# Sheet1.net
KiCad netlist of a schematic drawn in Altium Designer
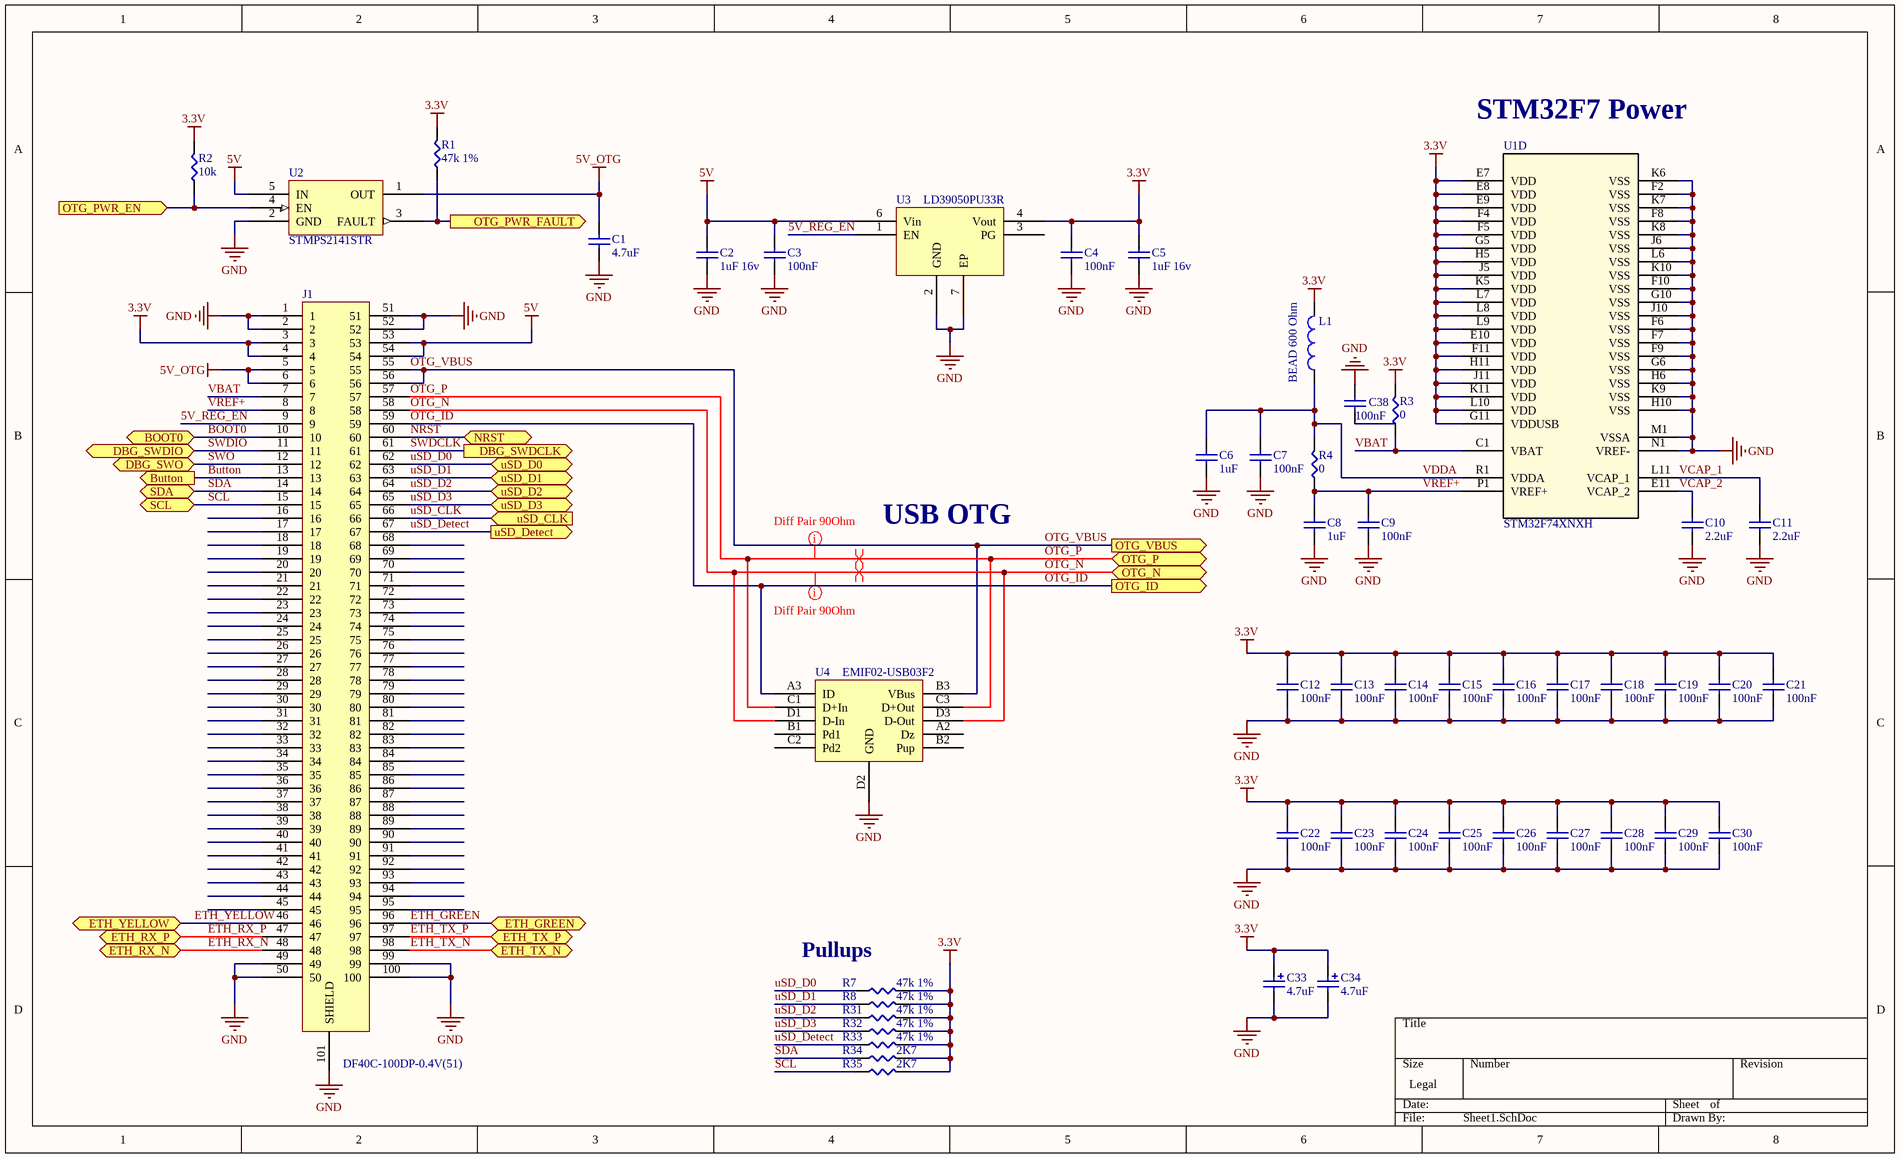
[diagram p0: Sheet1.SchDoc]

(export (version "E")
  (design (tool "Eeschema 10.0.6"))
  (components
    (comp (ref "C1")
      (value "4.7uF")
      (footprint "CAP0603X055M")
      (description "CAP CER 4.7UF 10V X5R 0603")
      (fields
        (field (name "MANUFACTURER") "Samsung Electro-Mechanics America, Inc.")
        (field (name "MANUFACTURER PART NUMBER") "CL10A475MP5LNNC")
      )
      (libsource (lib "Main") (part "CL10A475MP5LNNC"))
    )
    (comp (ref "C2")
      (value "1uF 16v")
      (footprint "CAP0603X055M")
      (description "CAP CER 1UF 16V Y5V 0603")
      (fields
        (field (name "MANUFACTURER") "Yageo")
        (field (name "MANUFACTURER PART NUMBER") "CC0603ZRY5V7BB105")
      )
      (libsource (lib "Main") (part "CC0603ZRY5V7BB105"))
    )
    (comp (ref "C3")
      (value "100nF")
      (footprint "CAP0402X04M")
      (description "CAP CER 0.1UF 16V X7R 0402")
      (fields
        (field (name "MANUFACTURER") "Murata Electronics North America")
        (field (name "MANUFACTURER PART NUMBER") "GRM155R71C104KA88J")
      )
      (libsource (lib "Main") (part "GRM155R71C104KA88J"))
    )
    (comp (ref "C4")
      (value "100nF")
      (footprint "CAP0402X04M")
      (description "CAP CER 0.1UF 16V X7R 0402")
      (fields
        (field (name "MANUFACTURER") "Murata Electronics North America")
        (field (name "MANUFACTURER PART NUMBER") "GRM155R71C104KA88J")
      )
      (libsource (lib "Main") (part "GRM155R71C104KA88J"))
    )
    (comp (ref "C5")
      (value "1uF 16v")
      (footprint "CAP0603X055M")
      (description "CAP CER 1UF 16V Y5V 0603")
      (fields
        (field (name "MANUFACTURER") "Yageo")
        (field (name "MANUFACTURER PART NUMBER") "CC0603ZRY5V7BB105")
      )
      (libsource (lib "Main") (part "CC0603ZRY5V7BB105"))
    )
    (comp (ref "C6")
      (value "1uF")
      (footprint "CAP0402X04M")
      (description "CAP CER 1UF 6.3V X5R 0402")
      (fields
        (field (name "MANUFACTURER") "Murata Electronics North America")
        (field (name "MANUFACTURER PART NUMBER") "GRM155R60J105KE19D")
      )
      (libsource (lib "Main") (part "GRM155R60J105KE19D"))
    )
    (comp (ref "C7")
      (value "100nF")
      (footprint "CAP0402X04M")
      (description "CAP CER 0.1UF 16V X7R 0402")
      (fields
        (field (name "MANUFACTURER") "Murata Electronics North America")
        (field (name "MANUFACTURER PART NUMBER") "GRM155R71C104KA88J")
      )
      (libsource (lib "Main") (part "GRM155R71C104KA88J"))
    )
    (comp (ref "C8")
      (value "1uF")
      (footprint "CAP0402X04M")
      (description "CAP CER 1UF 6.3V X5R 0402")
      (fields
        (field (name "MANUFACTURER") "Murata Electronics North America")
        (field (name "MANUFACTURER PART NUMBER") "GRM155R60J105KE19D")
      )
      (libsource (lib "Main") (part "GRM155R60J105KE19D"))
    )
    (comp (ref "C9")
      (value "100nF")
      (footprint "CAP0402X04M")
      (description "CAP CER 0.1UF 16V X7R 0402")
      (fields
        (field (name "MANUFACTURER") "Murata Electronics North America")
        (field (name "MANUFACTURER PART NUMBER") "GRM155R71C104KA88J")
      )
      (libsource (lib "Main") (part "GRM155R71C104KA88J"))
    )
    (comp (ref "C10")
      (value "2.2uF")
      (footprint "CAP0402X04ROUND")
      (description "CAP CER 2.2UF 6.3V X5R 0402")
      (fields
        (field (name "MANUFACTURER") "AVX Corporation")
        (field (name "MANUFACTURER PART NUMBER") "04026D225KAT2A")
      )
      (libsource (lib "Main") (part "04026D225KAT2A"))
    )
    (comp (ref "C11")
      (value "2.2uF")
      (footprint "CAP0402X04ROUND")
      (description "CAP CER 2.2UF 6.3V X5R 0402")
      (fields
        (field (name "MANUFACTURER") "AVX Corporation")
        (field (name "MANUFACTURER PART NUMBER") "04026D225KAT2A")
      )
      (libsource (lib "Main") (part "04026D225KAT2A"))
    )
    (comp (ref "C12")
      (value "100nF")
      (footprint "CAP0402X04ROUND")
      (description "CAP CER 0.1UF 16V X7R 0402")
      (fields
        (field (name "MANUFACTURER") "Murata Electronics North America")
        (field (name "MANUFACTURER PART NUMBER") "GRM155R71C104KA88J")
      )
      (libsource (lib "Main") (part "GRM155R71C104KA88J"))
    )
    (comp (ref "C13")
      (value "100nF")
      (footprint "CAP0402X04ROUND")
      (description "CAP CER 0.1UF 16V X7R 0402")
      (fields
        (field (name "MANUFACTURER") "Murata Electronics North America")
        (field (name "MANUFACTURER PART NUMBER") "GRM155R71C104KA88J")
      )
      (libsource (lib "Main") (part "GRM155R71C104KA88J"))
    )
    (comp (ref "C14")
      (value "100nF")
      (footprint "CAP0402X04ROUND")
      (description "CAP CER 0.1UF 16V X7R 0402")
      (fields
        (field (name "MANUFACTURER") "Murata Electronics North America")
        (field (name "MANUFACTURER PART NUMBER") "GRM155R71C104KA88J")
      )
      (libsource (lib "Main") (part "GRM155R71C104KA88J"))
    )
    (comp (ref "C15")
      (value "100nF")
      (footprint "CAP0402X04ROUND")
      (description "CAP CER 0.1UF 16V X7R 0402")
      (fields
        (field (name "MANUFACTURER") "Murata Electronics North America")
        (field (name "MANUFACTURER PART NUMBER") "GRM155R71C104KA88J")
      )
      (libsource (lib "Main") (part "GRM155R71C104KA88J"))
    )
    (comp (ref "C16")
      (value "100nF")
      (footprint "CAP0402X04ROUND")
      (description "CAP CER 0.1UF 16V X7R 0402")
      (fields
        (field (name "MANUFACTURER") "Murata Electronics North America")
        (field (name "MANUFACTURER PART NUMBER") "GRM155R71C104KA88J")
      )
      (libsource (lib "Main") (part "GRM155R71C104KA88J"))
    )
    (comp (ref "C17")
      (value "100nF")
      (footprint "CAP0402X04ROUND")
      (description "CAP CER 0.1UF 16V X7R 0402")
      (fields
        (field (name "MANUFACTURER") "Murata Electronics North America")
        (field (name "MANUFACTURER PART NUMBER") "GRM155R71C104KA88J")
      )
      (libsource (lib "Main") (part "GRM155R71C104KA88J"))
    )
    (comp (ref "C18")
      (value "100nF")
      (footprint "CAP0402X04ROUND")
      (description "CAP CER 0.1UF 16V X7R 0402")
      (fields
        (field (name "MANUFACTURER") "Murata Electronics North America")
        (field (name "MANUFACTURER PART NUMBER") "GRM155R71C104KA88J")
      )
      (libsource (lib "Main") (part "GRM155R71C104KA88J"))
    )
    (comp (ref "C19")
      (value "100nF")
      (footprint "CAP0402X04ROUND")
      (description "CAP CER 0.1UF 16V X7R 0402")
      (fields
        (field (name "MANUFACTURER") "Murata Electronics North America")
        (field (name "MANUFACTURER PART NUMBER") "GRM155R71C104KA88J")
      )
      (libsource (lib "Main") (part "GRM155R71C104KA88J"))
    )
    (comp (ref "C20")
      (value "100nF")
      (footprint "CAP0402X04ROUND")
      (description "CAP CER 0.1UF 16V X7R 0402")
      (fields
        (field (name "MANUFACTURER") "Murata Electronics North America")
        (field (name "MANUFACTURER PART NUMBER") "GRM155R71C104KA88J")
      )
      (libsource (lib "Main") (part "GRM155R71C104KA88J"))
    )
    (comp (ref "C21")
      (value "100nF")
      (footprint "CAP0402X04ROUND")
      (description "CAP CER 0.1UF 16V X7R 0402")
      (fields
        (field (name "MANUFACTURER") "Murata Electronics North America")
        (field (name "MANUFACTURER PART NUMBER") "GRM155R71C104KA88J")
      )
      (libsource (lib "Main") (part "GRM155R71C104KA88J"))
    )
    (comp (ref "C22")
      (value "100nF")
      (footprint "CAP0402X04ROUND")
      (description "CAP CER 0.1UF 16V X7R 0402")
      (fields
        (field (name "MANUFACTURER") "Murata Electronics North America")
        (field (name "MANUFACTURER PART NUMBER") "GRM155R71C104KA88J")
      )
      (libsource (lib "Main") (part "GRM155R71C104KA88J"))
    )
    (comp (ref "C23")
      (value "100nF")
      (footprint "CAP0402X04ROUND")
      (description "CAP CER 0.1UF 16V X7R 0402")
      (fields
        (field (name "MANUFACTURER") "Murata Electronics North America")
        (field (name "MANUFACTURER PART NUMBER") "GRM155R71C104KA88J")
      )
      (libsource (lib "Main") (part "GRM155R71C104KA88J"))
    )
    (comp (ref "C24")
      (value "100nF")
      (footprint "CAP0402X04ROUND")
      (description "CAP CER 0.1UF 16V X7R 0402")
      (fields
        (field (name "MANUFACTURER") "Murata Electronics North America")
        (field (name "MANUFACTURER PART NUMBER") "GRM155R71C104KA88J")
      )
      (libsource (lib "Main") (part "GRM155R71C104KA88J"))
    )
    (comp (ref "C25")
      (value "100nF")
      (footprint "CAP0402X04ROUND")
      (description "CAP CER 0.1UF 16V X7R 0402")
      (fields
        (field (name "MANUFACTURER") "Murata Electronics North America")
        (field (name "MANUFACTURER PART NUMBER") "GRM155R71C104KA88J")
      )
      (libsource (lib "Main") (part "GRM155R71C104KA88J"))
    )
    (comp (ref "C26")
      (value "100nF")
      (footprint "CAP0402X04ROUND")
      (description "CAP CER 0.1UF 16V X7R 0402")
      (fields
        (field (name "MANUFACTURER") "Murata Electronics North America")
        (field (name "MANUFACTURER PART NUMBER") "GRM155R71C104KA88J")
      )
      (libsource (lib "Main") (part "GRM155R71C104KA88J"))
    )
    (comp (ref "C27")
      (value "100nF")
      (footprint "CAP0402X04ROUND")
      (description "CAP CER 0.1UF 16V X7R 0402")
      (fields
        (field (name "MANUFACTURER") "Murata Electronics North America")
        (field (name "MANUFACTURER PART NUMBER") "GRM155R71C104KA88J")
      )
      (libsource (lib "Main") (part "GRM155R71C104KA88J"))
    )
    (comp (ref "C28")
      (value "100nF")
      (footprint "CAP0402X04ROUND")
      (description "CAP CER 0.1UF 16V X7R 0402")
      (fields
        (field (name "MANUFACTURER") "Murata Electronics North America")
        (field (name "MANUFACTURER PART NUMBER") "GRM155R71C104KA88J")
      )
      (libsource (lib "Main") (part "GRM155R71C104KA88J"))
    )
    (comp (ref "C29")
      (value "100nF")
      (footprint "CAP0402X04ROUND")
      (description "CAP CER 0.1UF 16V X7R 0402")
      (fields
        (field (name "MANUFACTURER") "Murata Electronics North America")
        (field (name "MANUFACTURER PART NUMBER") "GRM155R71C104KA88J")
      )
      (libsource (lib "Main") (part "GRM155R71C104KA88J"))
    )
    (comp (ref "C30")
      (value "100nF")
      (footprint "CAP0402X04ROUND")
      (description "CAP CER 0.1UF 16V X7R 0402")
      (fields
        (field (name "MANUFACTURER") "Murata Electronics North America")
        (field (name "MANUFACTURER PART NUMBER") "GRM155R71C104KA88J")
      )
      (libsource (lib "Main") (part "GRM155R71C104KA88J"))
    )
    (comp (ref "C33")
      (value "4.7uF")
      (footprint "CAPPOL0805X07N")
      (description "CAP TANT 4.7UF 10V 20% 0805")
      (fields
        (field (name "MANUFACTURER") "AVX Corporation")
        (field (name "MANUFACTURER PART NUMBER") "F921A475MPA")
      )
      (libsource (lib "Main") (part "F921A475MPA"))
    )
    (comp (ref "C34")
      (value "4.7uF")
      (footprint "CAPPOL0805X07N")
      (description "CAP TANT 4.7UF 10V 20% 0805")
      (fields
        (field (name "MANUFACTURER") "AVX Corporation")
        (field (name "MANUFACTURER PART NUMBER") "F921A475MPA")
      )
      (libsource (lib "Main") (part "F921A475MPA"))
    )
    (comp (ref "C38")
      (value "100nF")
      (footprint "CAP0402X04M")
      (description "CAP CER 0.1UF 16V X7R 0402")
      (fields
        (field (name "MANUFACTURER") "Murata Electronics North America")
        (field (name "MANUFACTURER PART NUMBER") "GRM155R71C104KA88J")
      )
      (libsource (lib "Main") (part "GRM155R71C104KA88J"))
    )
    (comp (ref "J1")
      (value "DF40C-100DP-0.4V(51)")
      (footprint "DF40C-100DP-0.4V(51)")
      (description "CONN HDR 100POS 0.4MM SMD GOLD")
      (fields (field (name "MANUFACTURER") "Hirose Electric Co Ltd"))
      (libsource (lib "Main") (part "DF40C-100DP-0.4V(51)"))
    )
    (comp (ref "L1")
      (value "BEAD 600 Ohm")
      (footprint "IND0603X055M")
      (description "FERRITE BEAD 600 OHM 0603 1LN")
      (fields
        (field (name "MANUFACTURER") "Taiyo Yuden")
        (field (name "MANUFACTURER PART NUMBER") "BK1608HW601-T")
      )
      (libsource (lib "Main") (part "BK1608HW601-T"))
    )
    (comp (ref "R1")
      (value "47k 1%")
      (footprint "RES0402X04M")
      (description "RES SMD 47K OHM 1% 1/10W 0402")
      (fields
        (field (name "MANUFACTURER") "Panasonic Electronic Components")
        (field (name "MANUFACTURER PART NUMBER") "ERJ-2RKF4702X")
      )
      (libsource (lib "Main") (part "ERJ-2RKF4702X"))
    )
    (comp (ref "R2")
      (value "10k")
      (footprint "RES0402X04M")
      (description "RES SMD 10K OHM 1% 1/16W 0402")
      (fields
        (field (name "MANUFACTURER") "Yageo")
        (field (name "MANUFACTURER PART NUMBER") "RC0402FR-0710KL")
      )
      (libsource (lib "Main") (part "RC0402FR-0710KL"))
    )
    (comp (ref "R3")
      (value "0")
      (footprint "RES0805X07M")
      (description "RES SMD 0.0 OHM JUMPER 1/8W 0805")
      (fields
        (field (name "MANUFACTURER") "Yageo")
        (field (name "MANUFACTURER PART NUMBER") "RC0805JR-070RL")
      )
      (libsource (lib "Main") (part "RC0805JR-070RL"))
    )
    (comp (ref "R4")
      (value "0")
      (footprint "RES0805X07M")
      (description "RES SMD 0.0 OHM JUMPER 1/8W 0805")
      (fields
        (field (name "MANUFACTURER") "Yageo")
        (field (name "MANUFACTURER PART NUMBER") "RC0805JR-070RL")
      )
      (libsource (lib "Main") (part "RC0805JR-070RL"))
    )
    (comp (ref "R7")
      (value "47k 1%")
      (footprint "RES0402X04M")
      (description "RES SMD 47K OHM 1% 1/10W 0402")
      (fields
        (field (name "MANUFACTURER") "Panasonic Electronic Components")
        (field (name "MANUFACTURER PART NUMBER") "ERJ-2RKF4702X")
      )
      (libsource (lib "Main") (part "ERJ-2RKF4702X"))
    )
    (comp (ref "R8")
      (value "47k 1%")
      (footprint "RES0402X04M")
      (description "RES SMD 47K OHM 1% 1/10W 0402")
      (fields
        (field (name "MANUFACTURER") "Panasonic Electronic Components")
        (field (name "MANUFACTURER PART NUMBER") "ERJ-2RKF4702X")
      )
      (libsource (lib "Main") (part "ERJ-2RKF4702X"))
    )
    (comp (ref "R31")
      (value "47k 1%")
      (footprint "RES0402X04M")
      (description "RES SMD 47K OHM 1% 1/10W 0402")
      (fields
        (field (name "MANUFACTURER") "Panasonic Electronic Components")
        (field (name "MANUFACTURER PART NUMBER") "ERJ-2RKF4702X")
      )
      (libsource (lib "Main") (part "ERJ-2RKF4702X"))
    )
    (comp (ref "R32")
      (value "47k 1%")
      (footprint "RES0402X04M")
      (description "RES SMD 47K OHM 1% 1/10W 0402")
      (fields
        (field (name "MANUFACTURER") "Panasonic Electronic Components")
        (field (name "MANUFACTURER PART NUMBER") "ERJ-2RKF4702X")
      )
      (libsource (lib "Main") (part "ERJ-2RKF4702X"))
    )
    (comp (ref "R33")
      (value "47k 1%")
      (footprint "RES0402X04M")
      (description "RES SMD 47K OHM 1% 1/10W 0402")
      (fields
        (field (name "MANUFACTURER") "Panasonic Electronic Components")
        (field (name "MANUFACTURER PART NUMBER") "ERJ-2RKF4702X")
      )
      (libsource (lib "Main") (part "ERJ-2RKF4702X"))
    )
    (comp (ref "R34")
      (value "2K7")
      (footprint "RES0402X04M")
      (description "RES SMD 2.7K OHM 1% 1/10W 0402")
      (fields
        (field (name "MANUFACTURER") "Panasonic Electronic Components")
        (field (name "MANUFACTURER PART NUMBER") "ERJ-2RKF2701X")
      )
      (libsource (lib "Main") (part "ERJ-2RKF2701X"))
    )
    (comp (ref "R35")
      (value "2K7")
      (footprint "RES0402X04M")
      (description "RES SMD 2.7K OHM 1% 1/10W 0402")
      (fields
        (field (name "MANUFACTURER") "Panasonic Electronic Components")
        (field (name "MANUFACTURER PART NUMBER") "ERJ-2RKF2701X")
      )
      (libsource (lib "Main") (part "ERJ-2RKF2701X"))
    )
    (comp (ref "U1")
      (value "STM32F74XNXH")
      (footprint "TFBGA-216_13X13")
      (description "Imported")
      (fields
        (field (name "MANUFACTURER") "STMicroelectronics")
        (field (name "MANUFACTURER PART NUMBER") "STM32F746NGH6")
        (field (name "COPYRIGHT") "Copyright (C) 2016 Accelerated Designs. All rights reserved")
      )
      (libsource (lib "Main") (part "STM32F74XNXH"))
    )
    (comp (ref "U2")
      (value "STMPS2141STR")
      (footprint "SOT95P280X145-5N")
      (description "IC PWR SWITCH 1CH 500MA SOT23-5")
      (fields (field (name "MANUFACTURER") "STMicroelectronics"))
      (libsource (lib "Main") (part "STMPS2141STR"))
    )
    (comp (ref "U3")
      (value "LD39050PU33R")
      (footprint "LD39050")
      (description "IC REG LDO 3.3V 0.5A 6DFN")
      (fields (field (name "MANUFACTURER") "STMicroelectronics"))
      (libsource (lib "Main") (part "LD39050PU33R"))
    )
    (comp (ref "U4")
      (value "EMIF02-USB03F2")
      (footprint "EMIF02-USB03F2")
      (description "FILTER RC(PI) 33 OHM/20PF SMD")
      (fields (field (name "MANUFACTURER") "STMicroelectronics"))
      (libsource (lib "Main") (part "EMIF02-USB03F2"))
    )
  )
  (nets
    (net (code "1") (name "/5V_REG_EN") (class "Default")
      (node (ref "J1") (pin "9") (pinfunction "9_9") (pintype "passive"))
      (node (ref "U3") (pin "1") (pinfunction "EN_1") (pintype "passive"))
    )
    (net (code "2") (name "/BOOT0") (class "Default")
      (node (ref "J1") (pin "10") (pinfunction "10_10") (pintype "passive"))
    )
    (net (code "3") (name "/Button") (class "Default")
      (node (ref "J1") (pin "13") (pinfunction "13_13") (pintype "passive"))
    )
    (net (code "4") (name "/ETH_GREEN") (class "Default")
      (node (ref "J1") (pin "96") (pinfunction "96_96") (pintype "passive"))
    )
    (net (code "5") (name "/ETH_RX_N") (class "Default")
      (node (ref "J1") (pin "48") (pinfunction "48_48") (pintype "passive"))
    )
    (net (code "6") (name "/ETH_RX_P") (class "Default")
      (node (ref "J1") (pin "47") (pinfunction "47_47") (pintype "passive"))
    )
    (net (code "7") (name "/ETH_TX_N") (class "Default")
      (node (ref "J1") (pin "98") (pinfunction "98_98") (pintype "passive"))
    )
    (net (code "8") (name "/ETH_TX_P") (class "Default")
      (node (ref "J1") (pin "97") (pinfunction "97_97") (pintype "passive"))
    )
    (net (code "9") (name "/ETH_YELLOW") (class "Default")
      (node (ref "J1") (pin "46") (pinfunction "46_46") (pintype "passive"))
    )
    (net (code "10") (name "/NRST") (class "Default")
      (node (ref "J1") (pin "60") (pinfunction "60_60") (pintype "passive"))
    )
    (net (code "11") (name "/OTG_ID") (class "Default")
      (node (ref "J1") (pin "59") (pinfunction "59_59") (pintype "passive"))
      (node (ref "U4") (pin "A3") (pinfunction "ID_A3") (pintype "passive"))
    )
    (net (code "12") (name "/OTG_N") (class "Default")
      (node (ref "J1") (pin "58") (pinfunction "58_58") (pintype "passive"))
      (node (ref "U4") (pin "D1") (pinfunction "D-In_D1") (pintype "passive"))
      (node (ref "U4") (pin "D3") (pinfunction "D-Out_D3") (pintype "passive"))
    )
    (net (code "13") (name "/OTG_P") (class "Default")
      (node (ref "J1") (pin "57") (pinfunction "57_57") (pintype "passive"))
      (node (ref "U4") (pin "C1") (pinfunction "D+In_C1") (pintype "passive"))
      (node (ref "U4") (pin "C3") (pinfunction "D+Out_C3") (pintype "passive"))
    )
    (net (code "14") (name "/OTG_PWR_EN") (class "Default")
      (node (ref "R2") (pin "1") (pinfunction "1_1") (pintype "passive"))
      (node (ref "U2") (pin "4") (pinfunction "EN_4") (pintype "input"))
    )
    (net (code "15") (name "/OTG_PWR_FAULT") (class "Default")
      (node (ref "R1") (pin "1") (pinfunction "1_1") (pintype "passive"))
      (node (ref "U2") (pin "3") (pinfunction "FAULT_3") (pintype "output"))
    )
    (net (code "16") (name "/OTG_VBUS") (class "Default")
      (node (ref "J1") (pin "55") (pinfunction "55_55") (pintype "passive"))
      (node (ref "J1") (pin "56") (pinfunction "56_56") (pintype "passive"))
      (node (ref "U4") (pin "B3") (pinfunction "VBus_B3") (pintype "passive"))
    )
    (net (code "17") (name "/SCL") (class "Default")
      (node (ref "J1") (pin "15") (pinfunction "15_15") (pintype "passive"))
      (node (ref "R35") (pin "1") (pinfunction "1_1") (pintype "passive"))
    )
    (net (code "18") (name "/SDA") (class "Default")
      (node (ref "J1") (pin "14") (pinfunction "14_14") (pintype "passive"))
      (node (ref "R34") (pin "1") (pinfunction "1_1") (pintype "passive"))
    )
    (net (code "19") (name "/SWDCLK") (class "Default")
      (node (ref "J1") (pin "61") (pinfunction "61_61") (pintype "passive"))
    )
    (net (code "20") (name "/SWDIO") (class "Default")
      (node (ref "J1") (pin "11") (pinfunction "11_11") (pintype "passive"))
    )
    (net (code "21") (name "/SWO") (class "Default")
      (node (ref "J1") (pin "12") (pinfunction "12_12") (pintype "passive"))
    )
    (net (code "22") (name "/VBAT") (class "Default")
      (node (ref "J1") (pin "7") (pinfunction "7_7") (pintype "passive"))
      (node (ref "R3") (pin "1") (pinfunction "1_1") (pintype "passive"))
      (node (ref "U1") (pin "C1") (pinfunction "VBAT_C1") (pintype "power_in"))
    )
    (net (code "23") (name "/VCAP_1") (class "Default")
      (node (ref "C11") (pin "2") (pinfunction "2_2") (pintype "passive"))
      (node (ref "U1") (pin "L11") (pinfunction "VCAP_1_L11") (pintype "power_in"))
    )
    (net (code "24") (name "/VCAP_2") (class "Default")
      (node (ref "C10") (pin "2") (pinfunction "2_2") (pintype "passive"))
      (node (ref "U1") (pin "E11") (pinfunction "VCAP_2_E11") (pintype "power_in"))
    )
    (net (code "25") (name "/VDDA") (class "Default")
      (node (ref "C6") (pin "2") (pinfunction "2_2") (pintype "passive"))
      (node (ref "C7") (pin "2") (pinfunction "2_2") (pintype "passive"))
      (node (ref "L1") (pin "1") (pinfunction "1_1") (pintype "passive"))
      (node (ref "R4") (pin "2") (pinfunction "2_2") (pintype "passive"))
      (node (ref "U1") (pin "R1") (pinfunction "VDDA_R1") (pintype "power_in"))
    )
    (net (code "26") (name "/VREF+") (class "Default")
      (node (ref "C8") (pin "2") (pinfunction "2_2") (pintype "passive"))
      (node (ref "C9") (pin "2") (pinfunction "2_2") (pintype "passive"))
      (node (ref "J1") (pin "8") (pinfunction "8_8") (pintype "passive"))
      (node (ref "R4") (pin "1") (pinfunction "1_1") (pintype "passive"))
      (node (ref "U1") (pin "P1") (pinfunction "VREF+_P1") (pintype "power_in"))
    )
    (net (code "27") (name "/uSD_CLK") (class "Default")
      (node (ref "J1") (pin "66") (pinfunction "66_66") (pintype "passive"))
    )
    (net (code "28") (name "/uSD_D0") (class "Default")
      (node (ref "J1") (pin "62") (pinfunction "62_62") (pintype "passive"))
      (node (ref "R7") (pin "1") (pinfunction "1_1") (pintype "passive"))
    )
    (net (code "29") (name "/uSD_D1") (class "Default")
      (node (ref "J1") (pin "63") (pinfunction "63_63") (pintype "passive"))
      (node (ref "R8") (pin "1") (pinfunction "1_1") (pintype "passive"))
    )
    (net (code "30") (name "/uSD_D2") (class "Default")
      (node (ref "J1") (pin "64") (pinfunction "64_64") (pintype "passive"))
      (node (ref "R31") (pin "1") (pinfunction "1_1") (pintype "passive"))
    )
    (net (code "31") (name "/uSD_D3") (class "Default")
      (node (ref "J1") (pin "65") (pinfunction "65_65") (pintype "passive"))
      (node (ref "R32") (pin "1") (pinfunction "1_1") (pintype "passive"))
    )
    (net (code "32") (name "/uSD_Detect") (class "Default")
      (node (ref "J1") (pin "67") (pinfunction "67_67") (pintype "passive"))
      (node (ref "R33") (pin "1") (pinfunction "1_1") (pintype "passive"))
    )
    (net (code "33") (name "3.3V") (class "Default")
      (node (ref "C12") (pin "2") (pinfunction "2_2") (pintype "passive"))
      (node (ref "C13") (pin "2") (pinfunction "2_2") (pintype "passive"))
      (node (ref "C14") (pin "2") (pinfunction "2_2") (pintype "passive"))
      (node (ref "C15") (pin "2") (pinfunction "2_2") (pintype "passive"))
      (node (ref "C16") (pin "2") (pinfunction "2_2") (pintype "passive"))
      (node (ref "C17") (pin "2") (pinfunction "2_2") (pintype "passive"))
      (node (ref "C18") (pin "2") (pinfunction "2_2") (pintype "passive"))
      (node (ref "C19") (pin "2") (pinfunction "2_2") (pintype "passive"))
      (node (ref "C20") (pin "2") (pinfunction "2_2") (pintype "passive"))
      (node (ref "C21") (pin "2") (pinfunction "2_2") (pintype "passive"))
      (node (ref "C22") (pin "2") (pinfunction "2_2") (pintype "passive"))
      (node (ref "C23") (pin "2") (pinfunction "2_2") (pintype "passive"))
      (node (ref "C24") (pin "2") (pinfunction "2_2") (pintype "passive"))
      (node (ref "C25") (pin "2") (pinfunction "2_2") (pintype "passive"))
      (node (ref "C26") (pin "2") (pinfunction "2_2") (pintype "passive"))
      (node (ref "C27") (pin "2") (pinfunction "2_2") (pintype "passive"))
      (node (ref "C28") (pin "2") (pinfunction "2_2") (pintype "passive"))
      (node (ref "C29") (pin "2") (pinfunction "2_2") (pintype "passive"))
      (node (ref "C30") (pin "2") (pinfunction "2_2") (pintype "passive"))
      (node (ref "C33") (pin "1") (pinfunction "1_1") (pintype "passive"))
      (node (ref "C34") (pin "1") (pinfunction "1_1") (pintype "passive"))
      (node (ref "C4") (pin "2") (pinfunction "2_2") (pintype "passive"))
      (node (ref "C5") (pin "2") (pinfunction "2_2") (pintype "passive"))
      (node (ref "J1") (pin "3") (pinfunction "3_3") (pintype "passive"))
      (node (ref "J1") (pin "4") (pinfunction "4_4") (pintype "passive"))
      (node (ref "L1") (pin "2") (pinfunction "2_2") (pintype "passive"))
      (node (ref "R1") (pin "2") (pinfunction "2_2") (pintype "passive"))
      (node (ref "R2") (pin "2") (pinfunction "2_2") (pintype "passive"))
      (node (ref "R3") (pin "2") (pinfunction "2_2") (pintype "passive"))
      (node (ref "R31") (pin "2") (pinfunction "2_2") (pintype "passive"))
      (node (ref "R32") (pin "2") (pinfunction "2_2") (pintype "passive"))
      (node (ref "R33") (pin "2") (pinfunction "2_2") (pintype "passive"))
      (node (ref "R34") (pin "2") (pinfunction "2_2") (pintype "passive"))
      (node (ref "R35") (pin "2") (pinfunction "2_2") (pintype "passive"))
      (node (ref "R7") (pin "2") (pinfunction "2_2") (pintype "passive"))
      (node (ref "R8") (pin "2") (pinfunction "2_2") (pintype "passive"))
      (node (ref "U1") (pin "E10") (pinfunction "VDD_E10") (pintype "power_in"))
      (node (ref "U1") (pin "E7") (pinfunction "VDD_E7") (pintype "power_in"))
      (node (ref "U1") (pin "E8") (pinfunction "VDD_E8") (pintype "power_in"))
      (node (ref "U1") (pin "E9") (pinfunction "VDD_E9") (pintype "power_in"))
      (node (ref "U1") (pin "F11") (pinfunction "VDD_F11") (pintype "power_in"))
      (node (ref "U1") (pin "F4") (pinfunction "VDD_F4") (pintype "power_in"))
      (node (ref "U1") (pin "F5") (pinfunction "VDD_F5") (pintype "power_in"))
      (node (ref "U1") (pin "G11") (pinfunction "VDDUSB_G11") (pintype "power_in"))
      (node (ref "U1") (pin "G5") (pinfunction "VDD_G5") (pintype "power_in"))
      (node (ref "U1") (pin "H11") (pinfunction "VDD_H11") (pintype "power_in"))
      (node (ref "U1") (pin "H5") (pinfunction "VDD_H5") (pintype "power_in"))
      (node (ref "U1") (pin "J11") (pinfunction "VDD_J11") (pintype "power_in"))
      (node (ref "U1") (pin "J5") (pinfunction "VDD_J5") (pintype "power_in"))
      (node (ref "U1") (pin "K11") (pinfunction "VDD_K11") (pintype "power_in"))
      (node (ref "U1") (pin "K5") (pinfunction "VDD_K5") (pintype "power_in"))
      (node (ref "U1") (pin "L10") (pinfunction "VDD_L10") (pintype "power_in"))
      (node (ref "U1") (pin "L7") (pinfunction "VDD_L7") (pintype "power_in"))
      (node (ref "U1") (pin "L8") (pinfunction "VDD_L8") (pintype "power_in"))
      (node (ref "U1") (pin "L9") (pinfunction "VDD_L9") (pintype "power_in"))
      (node (ref "U3") (pin "4") (pinfunction "Vout_4") (pintype "passive"))
    )
    (net (code "34") (name "5V") (class "Default")
      (node (ref "C2") (pin "2") (pinfunction "2_2") (pintype "passive"))
      (node (ref "C3") (pin "2") (pinfunction "2_2") (pintype "passive"))
      (node (ref "J1") (pin "53") (pinfunction "53_53") (pintype "passive"))
      (node (ref "J1") (pin "54") (pinfunction "54_54") (pintype "passive"))
      (node (ref "U2") (pin "5") (pinfunction "IN_5") (pintype "power_in"))
      (node (ref "U3") (pin "6") (pinfunction "Vin_6") (pintype "passive"))
    )
    (net (code "35") (name "5V_OTG") (class "Default")
      (node (ref "C1") (pin "2") (pinfunction "2_2") (pintype "passive"))
      (node (ref "J1") (pin "5") (pinfunction "5_5") (pintype "passive"))
      (node (ref "J1") (pin "6") (pinfunction "6_6") (pintype "passive"))
      (node (ref "U2") (pin "1") (pinfunction "OUT_1") (pintype "power_in"))
    )
    (net (code "36") (name "GND") (class "Default")
      (node (ref "C1") (pin "1") (pinfunction "1_1") (pintype "passive"))
      (node (ref "C10") (pin "1") (pinfunction "1_1") (pintype "passive"))
      (node (ref "C11") (pin "1") (pinfunction "1_1") (pintype "passive"))
      (node (ref "C12") (pin "1") (pinfunction "1_1") (pintype "passive"))
      (node (ref "C13") (pin "1") (pinfunction "1_1") (pintype "passive"))
      (node (ref "C14") (pin "1") (pinfunction "1_1") (pintype "passive"))
      (node (ref "C15") (pin "1") (pinfunction "1_1") (pintype "passive"))
      (node (ref "C16") (pin "1") (pinfunction "1_1") (pintype "passive"))
      (node (ref "C17") (pin "1") (pinfunction "1_1") (pintype "passive"))
      (node (ref "C18") (pin "1") (pinfunction "1_1") (pintype "passive"))
      (node (ref "C19") (pin "1") (pinfunction "1_1") (pintype "passive"))
      (node (ref "C2") (pin "1") (pinfunction "1_1") (pintype "passive"))
      (node (ref "C20") (pin "1") (pinfunction "1_1") (pintype "passive"))
      (node (ref "C21") (pin "1") (pinfunction "1_1") (pintype "passive"))
      (node (ref "C22") (pin "1") (pinfunction "1_1") (pintype "passive"))
      (node (ref "C23") (pin "1") (pinfunction "1_1") (pintype "passive"))
      (node (ref "C24") (pin "1") (pinfunction "1_1") (pintype "passive"))
      (node (ref "C25") (pin "1") (pinfunction "1_1") (pintype "passive"))
      (node (ref "C26") (pin "1") (pinfunction "1_1") (pintype "passive"))
      (node (ref "C27") (pin "1") (pinfunction "1_1") (pintype "passive"))
      (node (ref "C28") (pin "1") (pinfunction "1_1") (pintype "passive"))
      (node (ref "C29") (pin "1") (pinfunction "1_1") (pintype "passive"))
      (node (ref "C3") (pin "1") (pinfunction "1_1") (pintype "passive"))
      (node (ref "C30") (pin "1") (pinfunction "1_1") (pintype "passive"))
      (node (ref "C33") (pin "2") (pinfunction "2_2") (pintype "passive"))
      (node (ref "C34") (pin "2") (pinfunction "2_2") (pintype "passive"))
      (node (ref "C38") (pin "2") (pinfunction "2_2") (pintype "passive"))
      (node (ref "C4") (pin "1") (pinfunction "1_1") (pintype "passive"))
      (node (ref "C5") (pin "1") (pinfunction "1_1") (pintype "passive"))
      (node (ref "C6") (pin "1") (pinfunction "1_1") (pintype "passive"))
      (node (ref "C7") (pin "1") (pinfunction "1_1") (pintype "passive"))
      (node (ref "C8") (pin "1") (pinfunction "1_1") (pintype "passive"))
      (node (ref "C9") (pin "1") (pinfunction "1_1") (pintype "passive"))
      (node (ref "J1") (pin "1") (pinfunction "1_1") (pintype "passive"))
      (node (ref "J1") (pin "100") (pinfunction "100_100") (pintype "passive"))
      (node (ref "J1") (pin "101") (pinfunction "SHIELD_101") (pintype "passive"))
      (node (ref "J1") (pin "2") (pinfunction "2_2") (pintype "passive"))
      (node (ref "J1") (pin "49") (pinfunction "49_49") (pintype "passive"))
      (node (ref "J1") (pin "50") (pinfunction "50_50") (pintype "passive"))
      (node (ref "J1") (pin "51") (pinfunction "51_51") (pintype "passive"))
      (node (ref "J1") (pin "52") (pinfunction "52_52") (pintype "passive"))
      (node (ref "J1") (pin "99") (pinfunction "99_99") (pintype "passive"))
      (node (ref "U1") (pin "F10") (pinfunction "VSS_F10") (pintype "power_in"))
      (node (ref "U1") (pin "F2") (pinfunction "VSS_F2") (pintype "power_in"))
      (node (ref "U1") (pin "F6") (pinfunction "VSS_F6") (pintype "power_in"))
      (node (ref "U1") (pin "F7") (pinfunction "VSS_F7") (pintype "power_in"))
      (node (ref "U1") (pin "F8") (pinfunction "VSS_F8") (pintype "power_in"))
      (node (ref "U1") (pin "F9") (pinfunction "VSS_F9") (pintype "power_in"))
      (node (ref "U1") (pin "G10") (pinfunction "VSS_G10") (pintype "power_in"))
      (node (ref "U1") (pin "G6") (pinfunction "VSS_G6") (pintype "power_in"))
      (node (ref "U1") (pin "H10") (pinfunction "VSS_H10") (pintype "power_in"))
      (node (ref "U1") (pin "H6") (pinfunction "VSS_H6") (pintype "power_in"))
      (node (ref "U1") (pin "J10") (pinfunction "VSS_J10") (pintype "power_in"))
      (node (ref "U1") (pin "J6") (pinfunction "VSS_J6") (pintype "power_in"))
      (node (ref "U1") (pin "K10") (pinfunction "VSS_K10") (pintype "power_in"))
      (node (ref "U1") (pin "K6") (pinfunction "VSS_K6") (pintype "power_in"))
      (node (ref "U1") (pin "K7") (pinfunction "VSS_K7") (pintype "power_in"))
      (node (ref "U1") (pin "K8") (pinfunction "VSS_K8") (pintype "power_in"))
      (node (ref "U1") (pin "K9") (pinfunction "VSS_K9") (pintype "power_in"))
      (node (ref "U1") (pin "L6") (pinfunction "VSS_L6") (pintype "power_in"))
      (node (ref "U1") (pin "M1") (pinfunction "VSSA_M1") (pintype "power_in"))
      (node (ref "U1") (pin "N1") (pinfunction "VREF-_N1") (pintype "power_in"))
      (node (ref "U2") (pin "2") (pinfunction "GND_2") (pintype "power_in"))
      (node (ref "U3") (pin "2") (pinfunction "GND_2") (pintype "passive"))
      (node (ref "U3") (pin "7") (pinfunction "EP_7") (pintype "passive"))
      (node (ref "U4") (pin "D2") (pinfunction "GND_D2") (pintype "power_in"))
    )
    (net (code "37") (name "unconnected-(C38-Pad1)") (class "Default")
      (node (ref "C38") (pin "1") (pinfunction "1_1") (pintype "passive"))
    )
    (net (code "38") (name "unconnected-(J1-Pad16)") (class "Default")
      (node (ref "J1") (pin "16") (pinfunction "16_16") (pintype "passive"))
    )
    (net (code "39") (name "unconnected-(J1-Pad17)") (class "Default")
      (node (ref "J1") (pin "17") (pinfunction "17_17") (pintype "passive"))
    )
    (net (code "40") (name "unconnected-(J1-Pad18)") (class "Default")
      (node (ref "J1") (pin "18") (pinfunction "18_18") (pintype "passive"))
    )
    (net (code "41") (name "unconnected-(J1-Pad19)") (class "Default")
      (node (ref "J1") (pin "19") (pinfunction "19_19") (pintype "passive"))
    )
    (net (code "42") (name "unconnected-(J1-Pad20)") (class "Default")
      (node (ref "J1") (pin "20") (pinfunction "20_20") (pintype "passive"))
    )
    (net (code "43") (name "unconnected-(J1-Pad21)") (class "Default")
      (node (ref "J1") (pin "21") (pinfunction "21_21") (pintype "passive"))
    )
    (net (code "44") (name "unconnected-(J1-Pad22)") (class "Default")
      (node (ref "J1") (pin "22") (pinfunction "22_22") (pintype "passive"))
    )
    (net (code "45") (name "unconnected-(J1-Pad23)") (class "Default")
      (node (ref "J1") (pin "23") (pinfunction "23_23") (pintype "passive"))
    )
    (net (code "46") (name "unconnected-(J1-Pad24)") (class "Default")
      (node (ref "J1") (pin "24") (pinfunction "24_24") (pintype "passive"))
    )
    (net (code "47") (name "unconnected-(J1-Pad25)") (class "Default")
      (node (ref "J1") (pin "25") (pinfunction "25_25") (pintype "passive"))
    )
    (net (code "48") (name "unconnected-(J1-Pad26)") (class "Default")
      (node (ref "J1") (pin "26") (pinfunction "26_26") (pintype "passive"))
    )
    (net (code "49") (name "unconnected-(J1-Pad27)") (class "Default")
      (node (ref "J1") (pin "27") (pinfunction "27_27") (pintype "passive"))
    )
    (net (code "50") (name "unconnected-(J1-Pad28)") (class "Default")
      (node (ref "J1") (pin "28") (pinfunction "28_28") (pintype "passive"))
    )
    (net (code "51") (name "unconnected-(J1-Pad29)") (class "Default")
      (node (ref "J1") (pin "29") (pinfunction "29_29") (pintype "passive"))
    )
    (net (code "52") (name "unconnected-(J1-Pad30)") (class "Default")
      (node (ref "J1") (pin "30") (pinfunction "30_30") (pintype "passive"))
    )
    (net (code "53") (name "unconnected-(J1-Pad31)") (class "Default")
      (node (ref "J1") (pin "31") (pinfunction "31_31") (pintype "passive"))
    )
    (net (code "54") (name "unconnected-(J1-Pad32)") (class "Default")
      (node (ref "J1") (pin "32") (pinfunction "32_32") (pintype "passive"))
    )
    (net (code "55") (name "unconnected-(J1-Pad33)") (class "Default")
      (node (ref "J1") (pin "33") (pinfunction "33_33") (pintype "passive"))
    )
    (net (code "56") (name "unconnected-(J1-Pad34)") (class "Default")
      (node (ref "J1") (pin "34") (pinfunction "34_34") (pintype "passive"))
    )
    (net (code "57") (name "unconnected-(J1-Pad35)") (class "Default")
      (node (ref "J1") (pin "35") (pinfunction "35_35") (pintype "passive"))
    )
    (net (code "58") (name "unconnected-(J1-Pad36)") (class "Default")
      (node (ref "J1") (pin "36") (pinfunction "36_36") (pintype "passive"))
    )
    (net (code "59") (name "unconnected-(J1-Pad37)") (class "Default")
      (node (ref "J1") (pin "37") (pinfunction "37_37") (pintype "passive"))
    )
    (net (code "60") (name "unconnected-(J1-Pad38)") (class "Default")
      (node (ref "J1") (pin "38") (pinfunction "38_38") (pintype "passive"))
    )
    (net (code "61") (name "unconnected-(J1-Pad39)") (class "Default")
      (node (ref "J1") (pin "39") (pinfunction "39_39") (pintype "passive"))
    )
    (net (code "62") (name "unconnected-(J1-Pad40)") (class "Default")
      (node (ref "J1") (pin "40") (pinfunction "40_40") (pintype "passive"))
    )
    (net (code "63") (name "unconnected-(J1-Pad41)") (class "Default")
      (node (ref "J1") (pin "41") (pinfunction "41_41") (pintype "passive"))
    )
    (net (code "64") (name "unconnected-(J1-Pad42)") (class "Default")
      (node (ref "J1") (pin "42") (pinfunction "42_42") (pintype "passive"))
    )
    (net (code "65") (name "unconnected-(J1-Pad43)") (class "Default")
      (node (ref "J1") (pin "43") (pinfunction "43_43") (pintype "passive"))
    )
    (net (code "66") (name "unconnected-(J1-Pad44)") (class "Default")
      (node (ref "J1") (pin "44") (pinfunction "44_44") (pintype "passive"))
    )
    (net (code "67") (name "unconnected-(J1-Pad45)") (class "Default")
      (node (ref "J1") (pin "45") (pinfunction "45_45") (pintype "passive"))
    )
    (net (code "68") (name "unconnected-(J1-Pad68)") (class "Default")
      (node (ref "J1") (pin "68") (pinfunction "68_68") (pintype "passive"))
    )
    (net (code "69") (name "unconnected-(J1-Pad69)") (class "Default")
      (node (ref "J1") (pin "69") (pinfunction "69_69") (pintype "passive"))
    )
    (net (code "70") (name "unconnected-(J1-Pad70)") (class "Default")
      (node (ref "J1") (pin "70") (pinfunction "70_70") (pintype "passive"))
    )
    (net (code "71") (name "unconnected-(J1-Pad71)") (class "Default")
      (node (ref "J1") (pin "71") (pinfunction "71_71") (pintype "passive"))
    )
    (net (code "72") (name "unconnected-(J1-Pad72)") (class "Default")
      (node (ref "J1") (pin "72") (pinfunction "72_72") (pintype "passive"))
    )
    (net (code "73") (name "unconnected-(J1-Pad73)") (class "Default")
      (node (ref "J1") (pin "73") (pinfunction "73_73") (pintype "passive"))
    )
    (net (code "74") (name "unconnected-(J1-Pad74)") (class "Default")
      (node (ref "J1") (pin "74") (pinfunction "74_74") (pintype "passive"))
    )
    (net (code "75") (name "unconnected-(J1-Pad75)") (class "Default")
      (node (ref "J1") (pin "75") (pinfunction "75_75") (pintype "passive"))
    )
    (net (code "76") (name "unconnected-(J1-Pad76)") (class "Default")
      (node (ref "J1") (pin "76") (pinfunction "76_76") (pintype "passive"))
    )
    (net (code "77") (name "unconnected-(J1-Pad77)") (class "Default")
      (node (ref "J1") (pin "77") (pinfunction "77_77") (pintype "passive"))
    )
    (net (code "78") (name "unconnected-(J1-Pad78)") (class "Default")
      (node (ref "J1") (pin "78") (pinfunction "78_78") (pintype "passive"))
    )
    (net (code "79") (name "unconnected-(J1-Pad79)") (class "Default")
      (node (ref "J1") (pin "79") (pinfunction "79_79") (pintype "passive"))
    )
    (net (code "80") (name "unconnected-(J1-Pad80)") (class "Default")
      (node (ref "J1") (pin "80") (pinfunction "80_80") (pintype "passive"))
    )
    (net (code "81") (name "unconnected-(J1-Pad81)") (class "Default")
      (node (ref "J1") (pin "81") (pinfunction "81_81") (pintype "passive"))
    )
    (net (code "82") (name "unconnected-(J1-Pad82)") (class "Default")
      (node (ref "J1") (pin "82") (pinfunction "82_82") (pintype "passive"))
    )
    (net (code "83") (name "unconnected-(J1-Pad83)") (class "Default")
      (node (ref "J1") (pin "83") (pinfunction "83_83") (pintype "passive"))
    )
    (net (code "84") (name "unconnected-(J1-Pad84)") (class "Default")
      (node (ref "J1") (pin "84") (pinfunction "84_84") (pintype "passive"))
    )
    (net (code "85") (name "unconnected-(J1-Pad85)") (class "Default")
      (node (ref "J1") (pin "85") (pinfunction "85_85") (pintype "passive"))
    )
    (net (code "86") (name "unconnected-(J1-Pad86)") (class "Default")
      (node (ref "J1") (pin "86") (pinfunction "86_86") (pintype "passive"))
    )
    (net (code "87") (name "unconnected-(J1-Pad87)") (class "Default")
      (node (ref "J1") (pin "87") (pinfunction "87_87") (pintype "passive"))
    )
    (net (code "88") (name "unconnected-(J1-Pad88)") (class "Default")
      (node (ref "J1") (pin "88") (pinfunction "88_88") (pintype "passive"))
    )
    (net (code "89") (name "unconnected-(J1-Pad89)") (class "Default")
      (node (ref "J1") (pin "89") (pinfunction "89_89") (pintype "passive"))
    )
    (net (code "90") (name "unconnected-(J1-Pad90)") (class "Default")
      (node (ref "J1") (pin "90") (pinfunction "90_90") (pintype "passive"))
    )
    (net (code "91") (name "unconnected-(J1-Pad91)") (class "Default")
      (node (ref "J1") (pin "91") (pinfunction "91_91") (pintype "passive"))
    )
    (net (code "92") (name "unconnected-(J1-Pad92)") (class "Default")
      (node (ref "J1") (pin "92") (pinfunction "92_92") (pintype "passive"))
    )
    (net (code "93") (name "unconnected-(J1-Pad93)") (class "Default")
      (node (ref "J1") (pin "93") (pinfunction "93_93") (pintype "passive"))
    )
    (net (code "94") (name "unconnected-(J1-Pad94)") (class "Default")
      (node (ref "J1") (pin "94") (pinfunction "94_94") (pintype "passive"))
    )
    (net (code "95") (name "unconnected-(J1-Pad95)") (class "Default")
      (node (ref "J1") (pin "95") (pinfunction "95_95") (pintype "passive"))
    )
    (net (code "96") (name "unconnected-(U3-PG-Pad3)") (class "Default")
      (node (ref "U3") (pin "3") (pinfunction "PG_3") (pintype "passive"))
    )
    (net (code "97") (name "unconnected-(U4-Dz-PadA2)") (class "Default")
      (node (ref "U4") (pin "A2") (pinfunction "Dz_A2") (pintype "passive"))
    )
    (net (code "98") (name "unconnected-(U4-Pd1-PadB1)") (class "Default")
      (node (ref "U4") (pin "B1") (pinfunction "Pd1_B1") (pintype "passive"))
    )
    (net (code "99") (name "unconnected-(U4-Pd2-PadC2)") (class "Default")
      (node (ref "U4") (pin "C2") (pinfunction "Pd2_C2") (pintype "passive"))
    )
    (net (code "100") (name "unconnected-(U4-Pup-PadB2)") (class "Default")
      (node (ref "U4") (pin "B2") (pinfunction "Pup_B2") (pintype "passive"))
    )
  )
)
